# FOC_DRV8323.net
KiCad netlist of a schematic drawn in Altium Designer
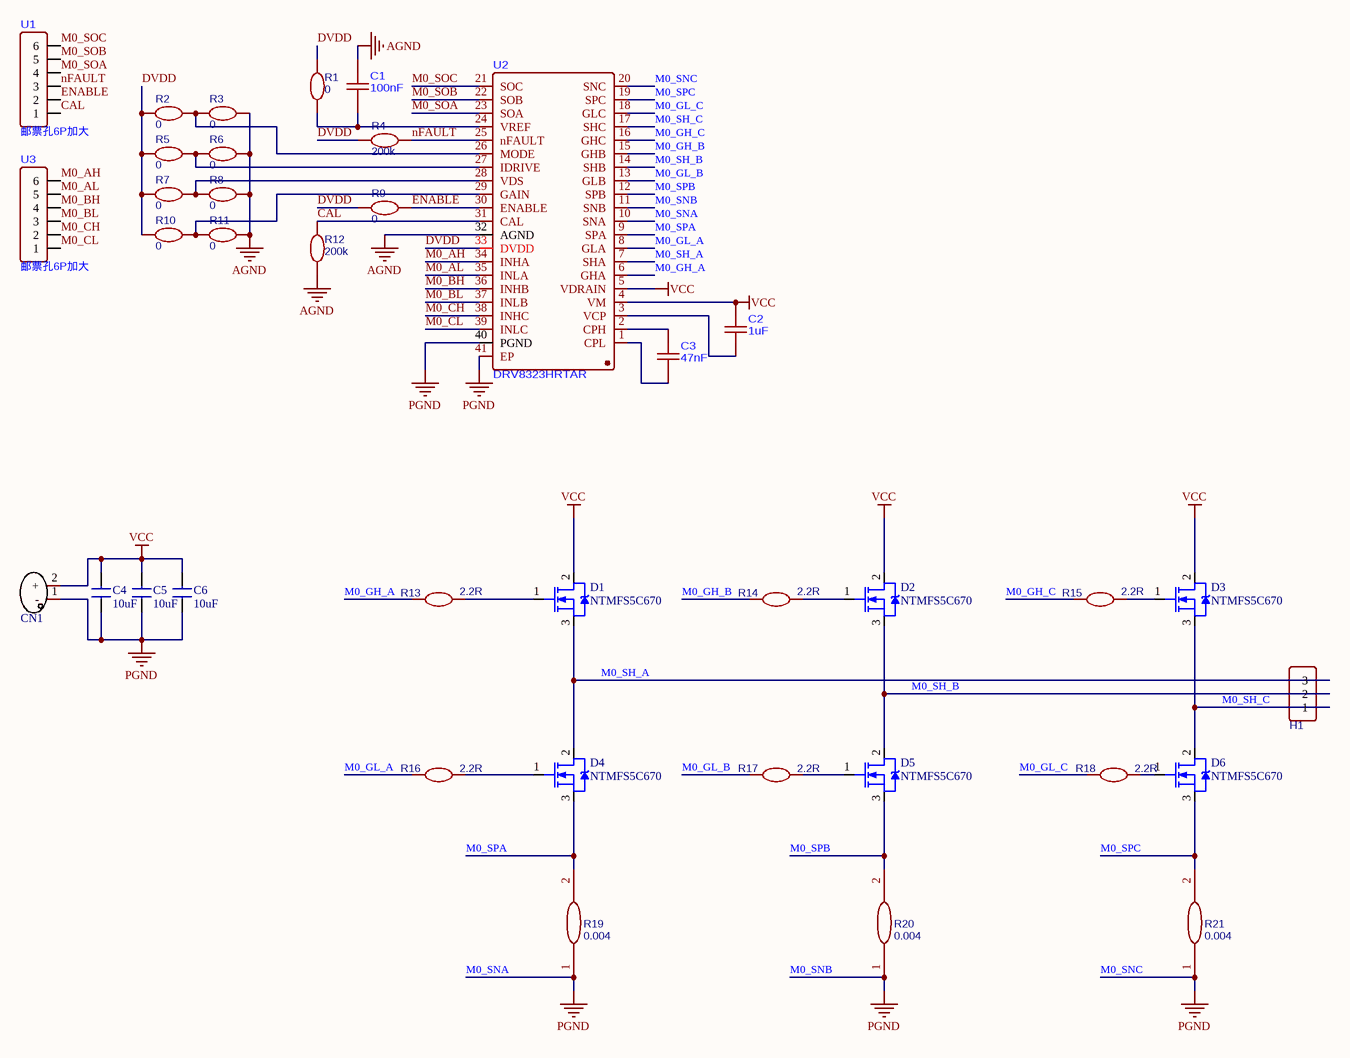
[diagram p0: FOC_DRV8323.SchDoc]

(export (version "E")
  (design (tool "Eeschema 10.0.6"))
  (components
    (comp (ref "C1") (value "100nF") (footprint "c0402") (libsource (lib "PETO") (part "CC0201JRX7R9BB101")))
    (comp (ref "C2") (value "1uF") (footprint "c0402") (libsource (lib "PETO") (part "CC0201JRX7R9BB101")))
    (comp (ref "C3") (value "47nF") (footprint "c0402") (libsource (lib "PETO") (part "CC0201JRX7R9BB101")))
    (comp (ref "C4")
      (value "10uF")
      (footprint "1210")
      (description "1210贴片电容")
      (libsource (lib "Integrated_Library1") (part "1210贴片电容"))
    )
    (comp (ref "C5")
      (value "10uF")
      (footprint "1210")
      (description "1210贴片电容")
      (libsource (lib "Integrated_Library1") (part "1210贴片电容"))
    )
    (comp (ref "C6")
      (value "10uF")
      (footprint "1210")
      (description "1210贴片电容")
      (libsource (lib "Integrated_Library1") (part "1210贴片电容"))
    )
    (comp (ref "CN1") (value "XT30_1") (footprint "XT30卧式焊盘") (libsource (lib "Schlib1") (part "XT30_1")))
    (comp (ref "D1")
      (value "NTMFS5C670")
      (footprint "pg-tdson-8")
      (description "N沟道MOS管")
      (fields (field (name "PUBLISHER") "Altium Limited"))
      (libsource (lib "En") (part "NTMFS5C670"))
    )
    (comp (ref "D2")
      (value "NTMFS5C670")
      (footprint "pg-tdson-8")
      (description "N沟道MOS管")
      (fields (field (name "PUBLISHER") "Altium Limited"))
      (libsource (lib "En") (part "NTMFS5C670"))
    )
    (comp (ref "D3")
      (value "NTMFS5C670")
      (footprint "pg-tdson-8")
      (description "N沟道MOS管")
      (fields (field (name "PUBLISHER") "Altium Limited"))
      (libsource (lib "En") (part "NTMFS5C670"))
    )
    (comp (ref "D4")
      (value "NTMFS5C670")
      (footprint "pg-tdson-8")
      (description "N沟道MOS管")
      (fields (field (name "PUBLISHER") "Altium Limited"))
      (libsource (lib "En") (part "NTMFS5C670"))
    )
    (comp (ref "D5")
      (value "NTMFS5C670")
      (footprint "pg-tdson-8")
      (description "N沟道MOS管")
      (fields (field (name "PUBLISHER") "Altium Limited"))
      (libsource (lib "En") (part "NTMFS5C670"))
    )
    (comp (ref "D6")
      (value "NTMFS5C670")
      (footprint "pg-tdson-8")
      (description "N沟道MOS管")
      (fields (field (name "PUBLISHER") "Altium Limited"))
      (libsource (lib "En") (part "NTMFS5C670"))
    )
    (comp (ref "H1")
      (value "MR30-M")
      (footprint "MR30")
      (fields (field (name "BOM_SUPPLIER PART") "C99873") (field (name "CONTRIBUTOR") "LCEDA_Lib"))
      (libsource (lib "altium-import") (part "root_2_MR30-M_"))
    )
    (comp (ref "R1")
      (value "0")
      (footprint "R0402")
      (fields
        (field (name "BOM_MANUFACTURER PART") "0603WAJ022JT5E")
        (field (name "BOM_SUPPLIER PART") "C25226")
      )
      (libsource (lib "altium-import") (part "root_3_2.2R_"))
    )
    (comp (ref "R2")
      (value "0")
      (footprint "R0402")
      (fields
        (field (name "BOM_MANUFACTURER PART") "0603WAJ022JT5E")
        (field (name "BOM_SUPPLIER PART") "C25226")
      )
      (libsource (lib "altium-import") (part "root_2_2.2R_"))
    )
    (comp (ref "R3")
      (value "0")
      (footprint "R0402")
      (fields
        (field (name "BOM_MANUFACTURER PART") "0603WAJ022JT5E")
        (field (name "BOM_SUPPLIER PART") "C25226")
      )
      (libsource (lib "altium-import") (part "root_2_2.2R_"))
    )
    (comp (ref "R4")
      (value "200k")
      (footprint "R0402")
      (fields
        (field (name "BOM_MANUFACTURER PART") "0603WAJ022JT5E")
        (field (name "BOM_SUPPLIER PART") "C25226")
      )
      (libsource (lib "altium-import") (part "root_0_2.2R_"))
    )
    (comp (ref "R5")
      (value "0")
      (footprint "R0402")
      (fields
        (field (name "BOM_MANUFACTURER PART") "0603WAJ022JT5E")
        (field (name "BOM_SUPPLIER PART") "C25226")
      )
      (libsource (lib "altium-import") (part "root_2_2.2R_"))
    )
    (comp (ref "R6")
      (value "0")
      (footprint "R0402")
      (fields
        (field (name "BOM_MANUFACTURER PART") "0603WAJ022JT5E")
        (field (name "BOM_SUPPLIER PART") "C25226")
      )
      (libsource (lib "altium-import") (part "root_2_2.2R_"))
    )
    (comp (ref "R7")
      (value "0")
      (footprint "R0402")
      (fields
        (field (name "BOM_MANUFACTURER PART") "0603WAJ022JT5E")
        (field (name "BOM_SUPPLIER PART") "C25226")
      )
      (libsource (lib "altium-import") (part "root_2_2.2R_"))
    )
    (comp (ref "R8")
      (value "0")
      (footprint "R0402")
      (fields
        (field (name "BOM_MANUFACTURER PART") "0603WAJ022JT5E")
        (field (name "BOM_SUPPLIER PART") "C25226")
      )
      (libsource (lib "altium-import") (part "root_2_2.2R_"))
    )
    (comp (ref "R9")
      (value "0")
      (footprint "R0402")
      (fields
        (field (name "BOM_MANUFACTURER PART") "0603WAJ022JT5E")
        (field (name "BOM_SUPPLIER PART") "C25226")
      )
      (libsource (lib "altium-import") (part "root_2_2.2R_"))
    )
    (comp (ref "R10")
      (value "0")
      (footprint "R0402")
      (fields
        (field (name "BOM_MANUFACTURER PART") "0603WAJ022JT5E")
        (field (name "BOM_SUPPLIER PART") "C25226")
      )
      (libsource (lib "altium-import") (part "root_2_2.2R_"))
    )
    (comp (ref "R11")
      (value "0")
      (footprint "R0402")
      (fields
        (field (name "BOM_MANUFACTURER PART") "0603WAJ022JT5E")
        (field (name "BOM_SUPPLIER PART") "C25226")
      )
      (libsource (lib "altium-import") (part "root_2_2.2R_"))
    )
    (comp (ref "R12")
      (value "200k")
      (footprint "R0402")
      (fields
        (field (name "BOM_MANUFACTURER PART") "0603WAJ022JT5E")
        (field (name "BOM_SUPPLIER PART") "C25226")
      )
      (libsource (lib "altium-import") (part "root_3_2.2R_"))
    )
    (comp (ref "R13")
      (value "2.2R")
      (footprint "R0402")
      (fields
        (field (name "BOM_MANUFACTURER PART") "0603WAJ022JT5E")
        (field (name "BOM_SUPPLIER PART") "C25226")
      )
      (libsource (lib "altium-import") (part "root_2_2.2R_"))
    )
    (comp (ref "R14")
      (value "2.2R")
      (footprint "R0402")
      (fields
        (field (name "BOM_MANUFACTURER PART") "0603WAJ022JT5E")
        (field (name "BOM_SUPPLIER PART") "C25226")
      )
      (libsource (lib "altium-import") (part "root_2_2.2R_"))
    )
    (comp (ref "R15")
      (value "2.2R")
      (footprint "R0402")
      (fields
        (field (name "BOM_MANUFACTURER PART") "0603WAJ022JT5E")
        (field (name "BOM_SUPPLIER PART") "C25226")
      )
      (libsource (lib "altium-import") (part "root_2_2.2R_"))
    )
    (comp (ref "R16")
      (value "2.2R")
      (footprint "R0402")
      (fields
        (field (name "BOM_MANUFACTURER PART") "0603WAJ022JT5E")
        (field (name "BOM_SUPPLIER PART") "C25226")
      )
      (libsource (lib "altium-import") (part "root_2_2.2R_"))
    )
    (comp (ref "R17")
      (value "2.2R")
      (footprint "R0402")
      (fields
        (field (name "BOM_MANUFACTURER PART") "0603WAJ022JT5E")
        (field (name "BOM_SUPPLIER PART") "C25226")
      )
      (libsource (lib "altium-import") (part "root_2_2.2R_"))
    )
    (comp (ref "R18")
      (value "2.2R")
      (footprint "R0402")
      (fields
        (field (name "BOM_MANUFACTURER PART") "0603WAJ022JT5E")
        (field (name "BOM_SUPPLIER PART") "C25226")
      )
      (libsource (lib "altium-import") (part "root_2_2.2R_"))
    )
    (comp (ref "R19")
      (value "0.004")
      (footprint "R0612")
      (fields
        (field (name "BOM_SUPPLIER PART") "C2681067")
        (field (name "BOM_MANUFACTURER PART") "LR2512-23R0005J4")
        (field (name "CONTRIBUTOR") "LCSC")
      )
      (libsource (lib "altium-import") (part "root_1_0.0005_"))
    )
    (comp (ref "R20")
      (value "0.004")
      (footprint "R0612")
      (fields
        (field (name "BOM_SUPPLIER PART") "C2681067")
        (field (name "BOM_MANUFACTURER PART") "LR2512-23R0005J4")
        (field (name "CONTRIBUTOR") "LCSC")
      )
      (libsource (lib "altium-import") (part "root_1_0.0005_"))
    )
    (comp (ref "R21")
      (value "0.004")
      (footprint "R0612")
      (fields
        (field (name "BOM_SUPPLIER PART") "C2681067")
        (field (name "BOM_MANUFACTURER PART") "LR2512-23R0005J4")
        (field (name "CONTRIBUTOR") "LCSC")
      )
      (libsource (lib "altium-import") (part "root_1_0.0005_"))
    )
    (comp (ref "U1")
      (value "邮票孔6P加大")
      (footprint "PCBComponent_1___pad")
      (libsource (lib "FOC_DRV8323") (part "邮票孔6P加大"))
    )
    (comp (ref "U2")
      (value "DRV8323HRTAR")
      (footprint "QFN-40_L6.0-W6.0-P0.50-BL-EP4.5")
      (libsource (lib "FOC_DRV8323") (part "DRV8323HRTAR"))
    )
    (comp (ref "U3")
      (value "邮票孔6P加大")
      (footprint "PCBComponent_1___pad")
      (libsource (lib "FOC_DRV8323") (part "邮票孔6P加大"))
    )
  )
  (nets
    (net (code "1") (name "/CAL") (class "Default")
      (node (ref "R12") (pin "1") (pinfunction "1_1") (pintype "passive"))
      (node (ref "U1") (pin "6") (pinfunction "1_6") (pintype "passive"))
      (node (ref "U2") (pin "31") (pinfunction "CAL_31") (pintype "passive"))
    )
    (net (code "2") (name "/DVDD") (class "Default")
      (node (ref "R1") (pin "1") (pinfunction "1_1") (pintype "passive"))
      (node (ref "R10") (pin "2") (pinfunction "2_2") (pintype "passive"))
      (node (ref "R2") (pin "2") (pinfunction "2_2") (pintype "passive"))
      (node (ref "R4") (pin "1") (pinfunction "1_1") (pintype "passive"))
      (node (ref "R5") (pin "2") (pinfunction "2_2") (pintype "passive"))
      (node (ref "R7") (pin "2") (pinfunction "2_2") (pintype "passive"))
      (node (ref "R9") (pin "2") (pinfunction "2_2") (pintype "passive"))
      (node (ref "U2") (pin "33") (pinfunction "DVDD_33") (pintype "passive"))
    )
    (net (code "3") (name "/ENABLE") (class "Default")
      (node (ref "R9") (pin "1") (pinfunction "1_1") (pintype "passive"))
      (node (ref "U1") (pin "5") (pinfunction "2_5") (pintype "passive"))
      (node (ref "U2") (pin "30") (pinfunction "ENABLE_30") (pintype "passive"))
    )
    (net (code "4") (name "/M0_AH") (class "Default")
      (node (ref "U2") (pin "34") (pinfunction "INHA_34") (pintype "passive"))
      (node (ref "U3") (pin "1") (pinfunction "6_1") (pintype "passive"))
    )
    (net (code "5") (name "/M0_AL") (class "Default")
      (node (ref "U2") (pin "35") (pinfunction "INLA_35") (pintype "passive"))
      (node (ref "U3") (pin "2") (pinfunction "5_2") (pintype "passive"))
    )
    (net (code "6") (name "/M0_BH") (class "Default")
      (node (ref "U2") (pin "36") (pinfunction "INHB_36") (pintype "passive"))
      (node (ref "U3") (pin "3") (pinfunction "4_3") (pintype "passive"))
    )
    (net (code "7") (name "/M0_BL") (class "Default")
      (node (ref "U2") (pin "37") (pinfunction "INLB_37") (pintype "passive"))
      (node (ref "U3") (pin "4") (pinfunction "3_4") (pintype "passive"))
    )
    (net (code "8") (name "/M0_CH") (class "Default")
      (node (ref "U2") (pin "38") (pinfunction "INHC_38") (pintype "passive"))
      (node (ref "U3") (pin "5") (pinfunction "2_5") (pintype "passive"))
    )
    (net (code "9") (name "/M0_CL") (class "Default")
      (node (ref "U2") (pin "39") (pinfunction "INLC_39") (pintype "passive"))
      (node (ref "U3") (pin "6") (pinfunction "1_6") (pintype "passive"))
    )
    (net (code "10") (name "/M0_GH_A") (class "Default")
      (node (ref "R13") (pin "2") (pinfunction "2_2") (pintype "passive"))
      (node (ref "U2") (pin "6") (pinfunction "GHA_6") (pintype "passive"))
    )
    (net (code "11") (name "/M0_GH_B") (class "Default")
      (node (ref "R14") (pin "2") (pinfunction "2_2") (pintype "passive"))
      (node (ref "U2") (pin "15") (pinfunction "GHB_15") (pintype "passive"))
    )
    (net (code "12") (name "/M0_GH_C") (class "Default")
      (node (ref "R15") (pin "2") (pinfunction "2_2") (pintype "passive"))
      (node (ref "U2") (pin "16") (pinfunction "GHC_16") (pintype "passive"))
    )
    (net (code "13") (name "/M0_GL_A") (class "Default")
      (node (ref "R16") (pin "2") (pinfunction "2_2") (pintype "passive"))
      (node (ref "U2") (pin "8") (pinfunction "GLA_8") (pintype "passive"))
    )
    (net (code "14") (name "/M0_GL_B") (class "Default")
      (node (ref "R17") (pin "2") (pinfunction "2_2") (pintype "passive"))
      (node (ref "U2") (pin "13") (pinfunction "GLB_13") (pintype "passive"))
    )
    (net (code "15") (name "/M0_GL_C") (class "Default")
      (node (ref "R18") (pin "2") (pinfunction "2_2") (pintype "passive"))
      (node (ref "U2") (pin "18") (pinfunction "GLC_18") (pintype "passive"))
    )
    (net (code "16") (name "/M0_SH_A") (class "Default")
      (node (ref "D1") (pin "3") (pinfunction "S_3") (pintype "passive"))
      (node (ref "D4") (pin "2") (pinfunction "D_2") (pintype "passive"))
      (node (ref "H1") (pin "3") (pinfunction "3_3") (pintype "passive"))
      (node (ref "U2") (pin "7") (pinfunction "SHA_7") (pintype "passive"))
    )
    (net (code "17") (name "/M0_SH_B") (class "Default")
      (node (ref "D2") (pin "3") (pinfunction "S_3") (pintype "passive"))
      (node (ref "D5") (pin "2") (pinfunction "D_2") (pintype "passive"))
      (node (ref "H1") (pin "2") (pinfunction "2_2") (pintype "passive"))
      (node (ref "U2") (pin "14") (pinfunction "SHB_14") (pintype "passive"))
    )
    (net (code "18") (name "/M0_SH_C") (class "Default")
      (node (ref "D3") (pin "3") (pinfunction "S_3") (pintype "passive"))
      (node (ref "D6") (pin "2") (pinfunction "D_2") (pintype "passive"))
      (node (ref "H1") (pin "1") (pinfunction "1_1") (pintype "passive"))
      (node (ref "U2") (pin "17") (pinfunction "SHC_17") (pintype "passive"))
    )
    (net (code "19") (name "/M0_SOA") (class "Default")
      (node (ref "U1") (pin "3") (pinfunction "4_3") (pintype "passive"))
      (node (ref "U2") (pin "23") (pinfunction "SOA_23") (pintype "passive"))
    )
    (net (code "20") (name "/M0_SOB") (class "Default")
      (node (ref "U1") (pin "2") (pinfunction "5_2") (pintype "passive"))
      (node (ref "U2") (pin "22") (pinfunction "SOB_22") (pintype "passive"))
    )
    (net (code "21") (name "/M0_SOC") (class "Default")
      (node (ref "U1") (pin "1") (pinfunction "6_1") (pintype "passive"))
      (node (ref "U2") (pin "21") (pinfunction "SOC_21") (pintype "passive"))
    )
    (net (code "22") (name "/M0_SPA") (class "Default")
      (node (ref "D4") (pin "3") (pinfunction "S_3") (pintype "passive"))
      (node (ref "R19") (pin "2") (pinfunction "2_2") (pintype "passive"))
      (node (ref "U2") (pin "9") (pinfunction "SPA_9") (pintype "passive"))
    )
    (net (code "23") (name "/M0_SPB") (class "Default")
      (node (ref "D5") (pin "3") (pinfunction "S_3") (pintype "passive"))
      (node (ref "R20") (pin "2") (pinfunction "2_2") (pintype "passive"))
      (node (ref "U2") (pin "12") (pinfunction "SPB_12") (pintype "passive"))
    )
    (net (code "24") (name "/M0_SPC") (class "Default")
      (node (ref "D6") (pin "3") (pinfunction "S_3") (pintype "passive"))
      (node (ref "R21") (pin "2") (pinfunction "2_2") (pintype "passive"))
      (node (ref "U2") (pin "19") (pinfunction "SPC_19") (pintype "passive"))
    )
    (net (code "25") (name "/nFAULT") (class "Default")
      (node (ref "R4") (pin "2") (pinfunction "2_2") (pintype "passive"))
      (node (ref "U1") (pin "4") (pinfunction "3_4") (pintype "passive"))
      (node (ref "U2") (pin "25") (pinfunction "nFAULT_25") (pintype "passive"))
    )
    (net (code "26") (name "AGND") (class "Default")
      (node (ref "C1") (pin "2") (pinfunction "2_2") (pintype "passive"))
      (node (ref "R11") (pin "1") (pinfunction "1_1") (pintype "passive"))
      (node (ref "R12") (pin "2") (pinfunction "2_2") (pintype "passive"))
      (node (ref "R3") (pin "1") (pinfunction "1_1") (pintype "passive"))
      (node (ref "R6") (pin "1") (pinfunction "1_1") (pintype "passive"))
      (node (ref "R8") (pin "1") (pinfunction "1_1") (pintype "passive"))
      (node (ref "U2") (pin "32") (pinfunction "AGND_32") (pintype "passive"))
    )
    (net (code "27") (name "Net-(D1-G)") (class "Default")
      (node (ref "D1") (pin "1") (pinfunction "G_1") (pintype "passive"))
      (node (ref "R13") (pin "1") (pinfunction "1_1") (pintype "passive"))
    )
    (net (code "28") (name "Net-(D2-G)") (class "Default")
      (node (ref "D2") (pin "1") (pinfunction "G_1") (pintype "passive"))
      (node (ref "R14") (pin "1") (pinfunction "1_1") (pintype "passive"))
    )
    (net (code "29") (name "Net-(D3-G)") (class "Default")
      (node (ref "D3") (pin "1") (pinfunction "G_1") (pintype "passive"))
      (node (ref "R15") (pin "1") (pinfunction "1_1") (pintype "passive"))
    )
    (net (code "30") (name "Net-(D4-G)") (class "Default")
      (node (ref "D4") (pin "1") (pinfunction "G_1") (pintype "passive"))
      (node (ref "R16") (pin "1") (pinfunction "1_1") (pintype "passive"))
    )
    (net (code "31") (name "Net-(D5-G)") (class "Default")
      (node (ref "D5") (pin "1") (pinfunction "G_1") (pintype "passive"))
      (node (ref "R17") (pin "1") (pinfunction "1_1") (pintype "passive"))
    )
    (net (code "32") (name "Net-(D6-G)") (class "Default")
      (node (ref "D6") (pin "1") (pinfunction "G_1") (pintype "passive"))
      (node (ref "R18") (pin "1") (pinfunction "1_1") (pintype "passive"))
    )
    (net (code "33") (name "Net-(U2-CPH)") (class "Default")
      (node (ref "C3") (pin "2") (pinfunction "2_2") (pintype "passive"))
      (node (ref "U2") (pin "2") (pinfunction "CPH_2") (pintype "passive"))
    )
    (net (code "34") (name "Net-(U2-CPL)") (class "Default")
      (node (ref "C3") (pin "1") (pinfunction "1_1") (pintype "passive"))
      (node (ref "U2") (pin "1") (pinfunction "CPL_1") (pintype "passive"))
    )
    (net (code "35") (name "Net-(U2-GAIN)") (class "Default")
      (node (ref "R10") (pin "1") (pinfunction "1_1") (pintype "passive"))
      (node (ref "R11") (pin "2") (pinfunction "2_2") (pintype "passive"))
      (node (ref "U2") (pin "29") (pinfunction "GAIN_29") (pintype "passive"))
    )
    (net (code "36") (name "Net-(U2-IDRIVE)") (class "Default")
      (node (ref "R5") (pin "1") (pinfunction "1_1") (pintype "passive"))
      (node (ref "R6") (pin "2") (pinfunction "2_2") (pintype "passive"))
      (node (ref "U2") (pin "27") (pinfunction "IDRIVE_27") (pintype "passive"))
    )
    (net (code "37") (name "Net-(U2-MODE)") (class "Default")
      (node (ref "R2") (pin "1") (pinfunction "1_1") (pintype "passive"))
      (node (ref "R3") (pin "2") (pinfunction "2_2") (pintype "passive"))
      (node (ref "U2") (pin "26") (pinfunction "MODE_26") (pintype "passive"))
    )
    (net (code "38") (name "Net-(U2-VCP)") (class "Default")
      (node (ref "C2") (pin "1") (pinfunction "1_1") (pintype "passive"))
      (node (ref "U2") (pin "3") (pinfunction "VCP_3") (pintype "passive"))
    )
    (net (code "39") (name "Net-(U2-VDS)") (class "Default")
      (node (ref "R7") (pin "1") (pinfunction "1_1") (pintype "passive"))
      (node (ref "R8") (pin "2") (pinfunction "2_2") (pintype "passive"))
      (node (ref "U2") (pin "28") (pinfunction "VDS_28") (pintype "passive"))
    )
    (net (code "40") (name "Net-(U2-VREF)") (class "Default")
      (node (ref "C1") (pin "1") (pinfunction "1_1") (pintype "passive"))
      (node (ref "R1") (pin "2") (pinfunction "2_2") (pintype "passive"))
      (node (ref "U2") (pin "24") (pinfunction "VREF_24") (pintype "passive"))
    )
    (net (code "41") (name "PGND") (class "Default")
      (node (ref "C4") (pin "1") (pinfunction "1_1") (pintype "passive"))
      (node (ref "C5") (pin "1") (pinfunction "1_1") (pintype "passive"))
      (node (ref "C6") (pin "1") (pinfunction "1_1") (pintype "passive"))
      (node (ref "CN1") (pin "1") (pinfunction "-_1") (pintype "passive"))
      (node (ref "R19") (pin "1") (pinfunction "1_1") (pintype "passive"))
      (node (ref "R20") (pin "1") (pinfunction "1_1") (pintype "passive"))
      (node (ref "R21") (pin "1") (pinfunction "1_1") (pintype "passive"))
      (node (ref "U2") (pin "10") (pinfunction "SNA_10") (pintype "passive"))
      (node (ref "U2") (pin "11") (pinfunction "SNB_11") (pintype "passive"))
      (node (ref "U2") (pin "20") (pinfunction "SNC_20") (pintype "passive"))
      (node (ref "U2") (pin "40") (pinfunction "PGND_40") (pintype "passive"))
      (node (ref "U2") (pin "41") (pinfunction "EP_41") (pintype "passive"))
    )
    (net (code "42") (name "VCC") (class "Default")
      (node (ref "C2") (pin "2") (pinfunction "2_2") (pintype "passive"))
      (node (ref "C4") (pin "2") (pinfunction "2_2") (pintype "passive"))
      (node (ref "C5") (pin "2") (pinfunction "2_2") (pintype "passive"))
      (node (ref "C6") (pin "2") (pinfunction "2_2") (pintype "passive"))
      (node (ref "CN1") (pin "2") (pinfunction "+_2") (pintype "passive"))
      (node (ref "D1") (pin "2") (pinfunction "D_2") (pintype "passive"))
      (node (ref "D2") (pin "2") (pinfunction "D_2") (pintype "passive"))
      (node (ref "D3") (pin "2") (pinfunction "D_2") (pintype "passive"))
      (node (ref "U2") (pin "4") (pinfunction "VM_4") (pintype "passive"))
      (node (ref "U2") (pin "5") (pinfunction "VDRAIN_5") (pintype "passive"))
    )
  )
)
